# al3lg.net
KiCad netlist of a schematic drawn in EAGLE
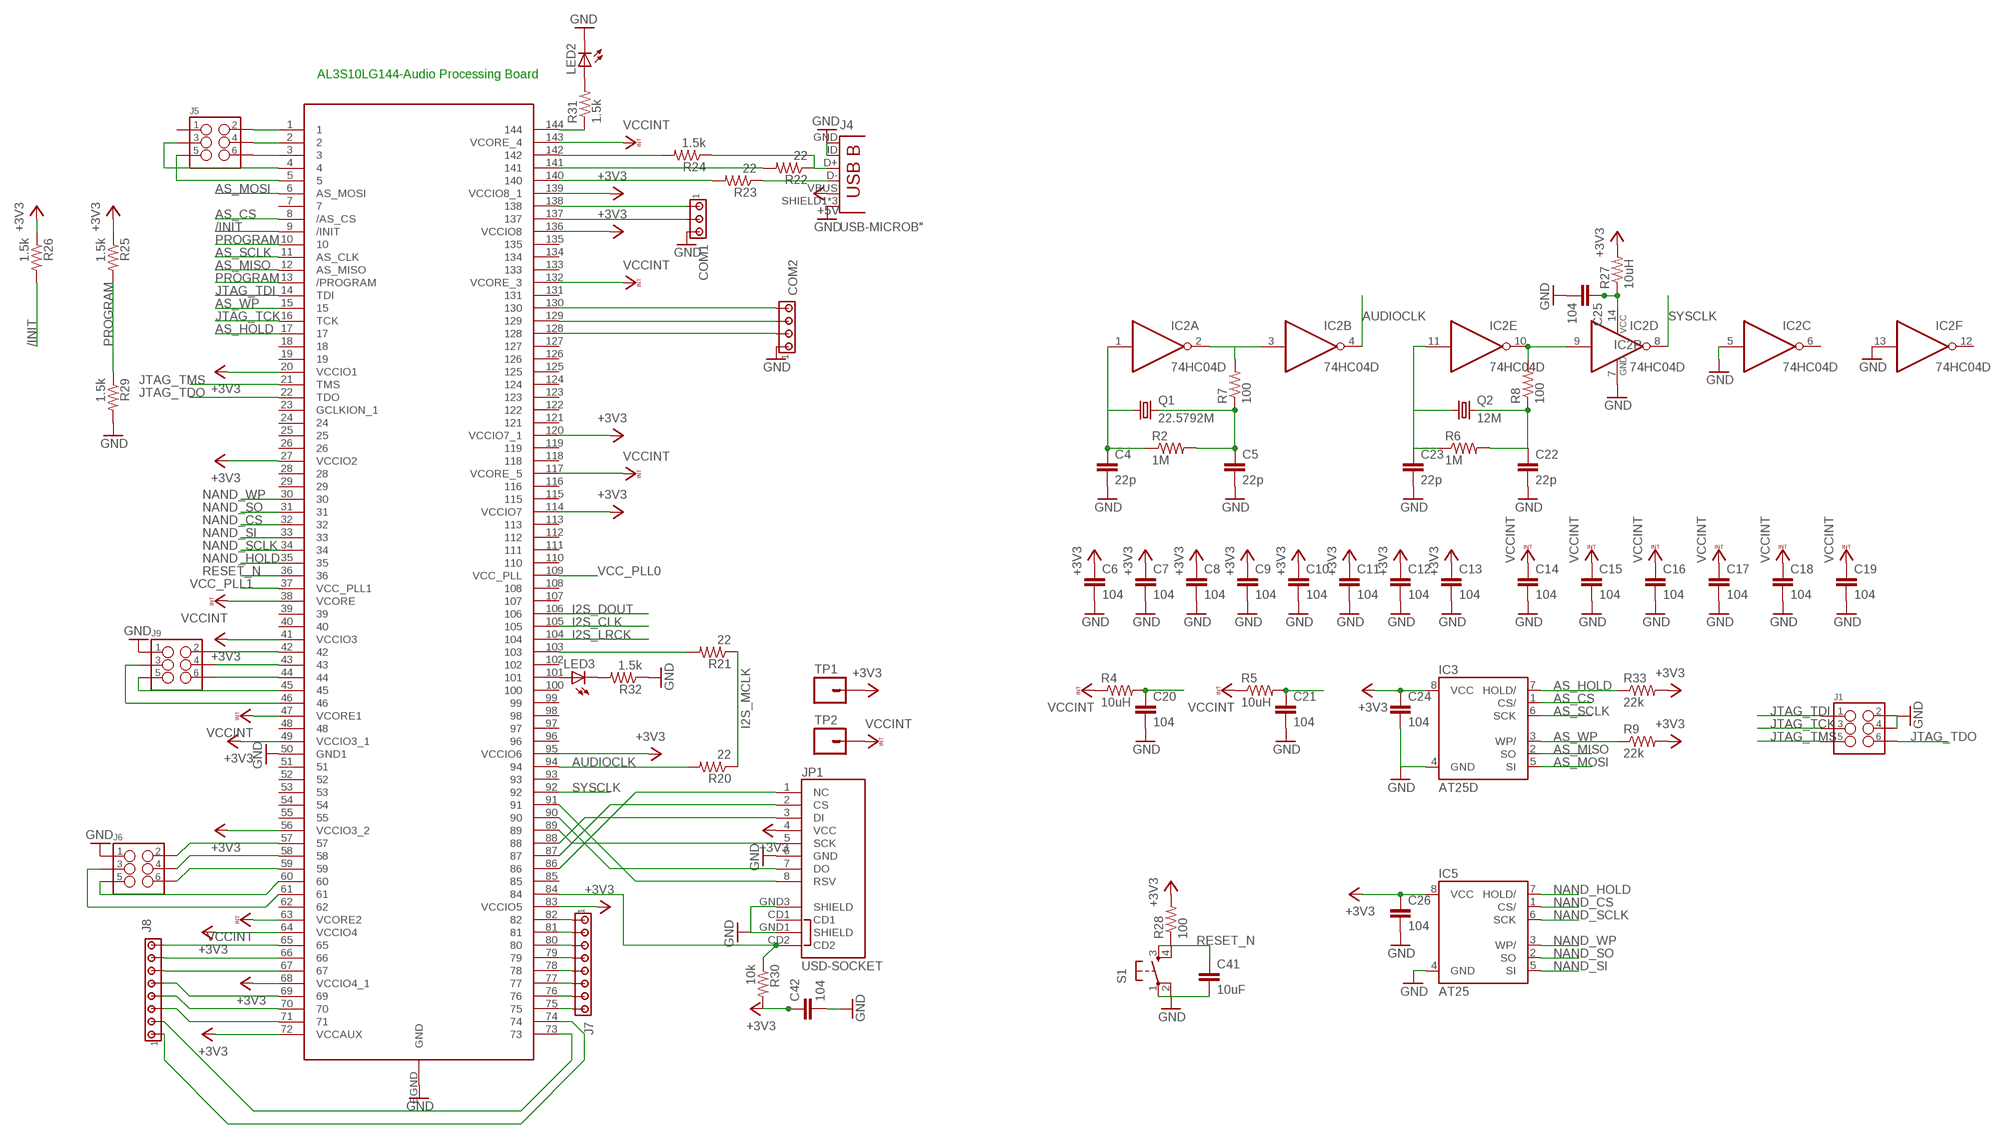
[diagram p0: schematic, sheet 1]
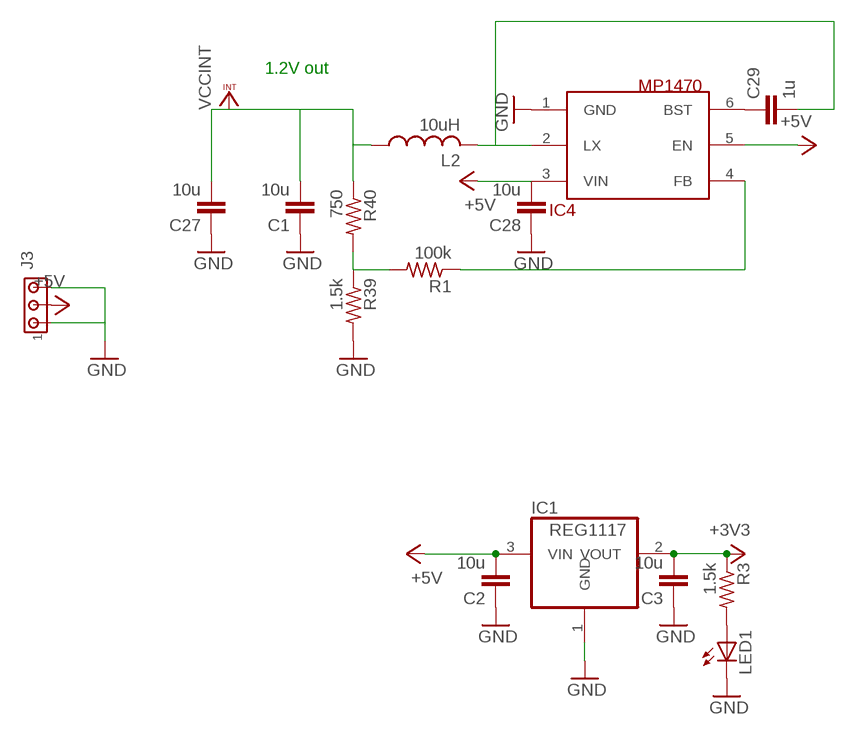
[diagram p1: schematic, sheet 2]
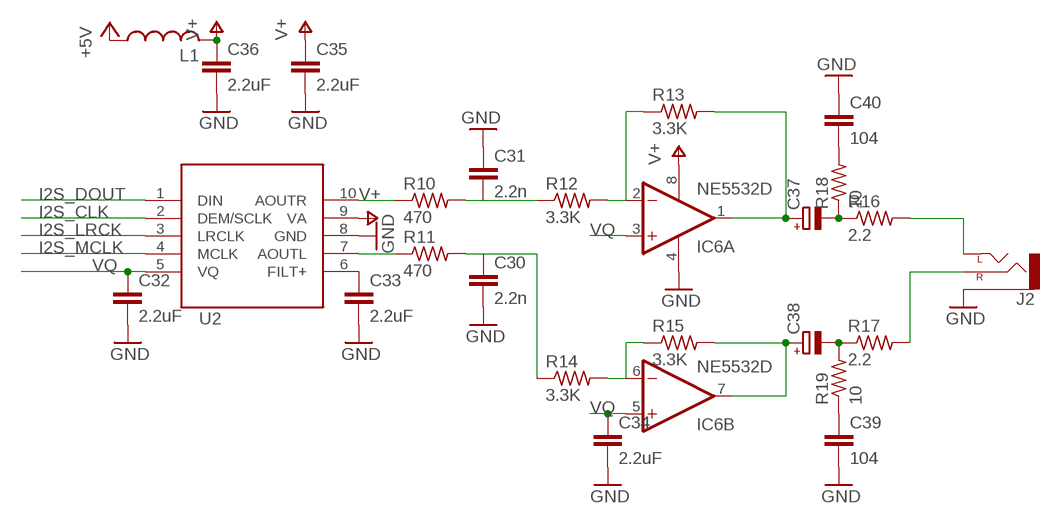
[diagram p2: schematic, sheet 3]

(export (version "E")
  (design (tool "Eeschema 10.0.6"))
  (components
    (comp (ref "C30")
      (value "2.2n")
      (footprint "eagle-import:C0805")
      (libsource (lib "eagle-import") (part "C-EUC0805"))
    )
    (comp (ref "C31")
      (value "2.2n")
      (footprint "eagle-import:C0805")
      (libsource (lib "eagle-import") (part "C-EUC0805"))
    )
    (comp (ref "C32")
      (value "2.2uF")
      (footprint "eagle-import:C0805")
      (libsource (lib "eagle-import") (part "C-EUC0805"))
    )
    (comp (ref "C33")
      (value "2.2uF")
      (footprint "eagle-import:C0805")
      (libsource (lib "eagle-import") (part "C-EUC0805"))
    )
    (comp (ref "C34")
      (value "2.2uF")
      (footprint "eagle-import:C0805")
      (libsource (lib "eagle-import") (part "C-EUC0805"))
    )
    (comp (ref "C35")
      (value "2.2uF")
      (footprint "eagle-import:C0805")
      (libsource (lib "eagle-import") (part "C-EUC0805"))
    )
    (comp (ref "C36")
      (value "2.2uF")
      (footprint "eagle-import:C0805")
      (libsource (lib "eagle-import") (part "C-EUC0805"))
    )
    (comp (ref "C37")
      (value "CPOL-EUE2.5-7")
      (footprint "eagle-import:E2,5-7")
      (libsource (lib "eagle-import") (part "CPOL-EUE2.5-7"))
    )
    (comp (ref "C38")
      (value "CPOL-EUE2.5-7")
      (footprint "eagle-import:E2,5-7")
      (libsource (lib "eagle-import") (part "CPOL-EUE2.5-7"))
    )
    (comp (ref "C39")
      (value "104")
      (footprint "eagle-import:C0805")
      (libsource (lib "eagle-import") (part "C-EUC0805"))
    )
    (comp (ref "C40")
      (value "104")
      (footprint "eagle-import:C0805")
      (libsource (lib "eagle-import") (part "C-EUC0805"))
    )
    (comp (ref "IC6")
      (value "NE5532D")
      (footprint "eagle-import:SO08")
      (libsource (lib "eagle-import") (part "NE5532D"))
    )
    (comp (ref "J2")
      (value "AUDIO-JACKPTH")
      (footprint "eagle-import:AUDIO-JACK")
      (libsource (lib "eagle-import") (part "AUDIO-JACKPTH"))
    )
    (comp (ref "L1")
      (value "L-USL4532P")
      (footprint "eagle-import:L4532P")
      (libsource (lib "eagle-import") (part "L-USL4532P"))
    )
    (comp (ref "R10")
      (value "470")
      (footprint "eagle-import:R0805")
      (libsource (lib "eagle-import") (part "R-US_R0805"))
    )
    (comp (ref "R11")
      (value "470")
      (footprint "eagle-import:R0805")
      (libsource (lib "eagle-import") (part "R-US_R0805"))
    )
    (comp (ref "R12")
      (value "3.3K")
      (footprint "eagle-import:R0805")
      (libsource (lib "eagle-import") (part "R-US_R0805"))
    )
    (comp (ref "R13")
      (value "3.3K")
      (footprint "eagle-import:R0805")
      (libsource (lib "eagle-import") (part "R-US_R0805"))
    )
    (comp (ref "R14")
      (value "3.3K")
      (footprint "eagle-import:R0805")
      (libsource (lib "eagle-import") (part "R-US_R0805"))
    )
    (comp (ref "R15")
      (value "3.3K")
      (footprint "eagle-import:R0805")
      (libsource (lib "eagle-import") (part "R-US_R0805"))
    )
    (comp (ref "R16")
      (value "2.2")
      (footprint "eagle-import:R0805")
      (libsource (lib "eagle-import") (part "R-US_R0805"))
    )
    (comp (ref "R17")
      (value "2.2")
      (footprint "eagle-import:R0805")
      (libsource (lib "eagle-import") (part "R-US_R0805"))
    )
    (comp (ref "R18")
      (value "10")
      (footprint "eagle-import:R0805")
      (libsource (lib "eagle-import") (part "R-US_R0805"))
    )
    (comp (ref "R19")
      (value "10")
      (footprint "eagle-import:R0805")
      (libsource (lib "eagle-import") (part "R-US_R0805"))
    )
    (comp (ref "U2")
      (value "CS4344")
      (footprint "eagle-import:TSSOP10")
      (libsource (lib "eagle-import") (part "CS4344"))
    )
    (comp (ref "C4")
      (value "22p")
      (footprint "eagle-import:C0805")
      (libsource (lib "eagle-import") (part "C-EUC0805"))
    )
    (comp (ref "C5")
      (value "22p")
      (footprint "eagle-import:C0805")
      (libsource (lib "eagle-import") (part "C-EUC0805"))
    )
    (comp (ref "C6")
      (value "104")
      (footprint "eagle-import:C0805")
      (libsource (lib "eagle-import") (part "C-EUC0805"))
    )
    (comp (ref "C7")
      (value "104")
      (footprint "eagle-import:C0805")
      (libsource (lib "eagle-import") (part "C-EUC0805"))
    )
    (comp (ref "C8")
      (value "104")
      (footprint "eagle-import:C0805")
      (libsource (lib "eagle-import") (part "C-EUC0805"))
    )
    (comp (ref "C9")
      (value "104")
      (footprint "eagle-import:C0805")
      (libsource (lib "eagle-import") (part "C-EUC0805"))
    )
    (comp (ref "C10")
      (value "104")
      (footprint "eagle-import:C0805")
      (libsource (lib "eagle-import") (part "C-EUC0805"))
    )
    (comp (ref "C11")
      (value "104")
      (footprint "eagle-import:C0805")
      (libsource (lib "eagle-import") (part "C-EUC0805"))
    )
    (comp (ref "C12")
      (value "104")
      (footprint "eagle-import:C0805")
      (libsource (lib "eagle-import") (part "C-EUC0805"))
    )
    (comp (ref "C13")
      (value "104")
      (footprint "eagle-import:C0805")
      (libsource (lib "eagle-import") (part "C-EUC0805"))
    )
    (comp (ref "C14")
      (value "104")
      (footprint "eagle-import:C0805")
      (libsource (lib "eagle-import") (part "C-EUC0805"))
    )
    (comp (ref "C15")
      (value "104")
      (footprint "eagle-import:C0805")
      (libsource (lib "eagle-import") (part "C-EUC0805"))
    )
    (comp (ref "C16")
      (value "104")
      (footprint "eagle-import:C0805")
      (libsource (lib "eagle-import") (part "C-EUC0805"))
    )
    (comp (ref "C17")
      (value "104")
      (footprint "eagle-import:C0805")
      (libsource (lib "eagle-import") (part "C-EUC0805"))
    )
    (comp (ref "C18")
      (value "104")
      (footprint "eagle-import:C0805")
      (libsource (lib "eagle-import") (part "C-EUC0805"))
    )
    (comp (ref "C19")
      (value "104")
      (footprint "eagle-import:C0805")
      (libsource (lib "eagle-import") (part "C-EUC0805"))
    )
    (comp (ref "C20")
      (value "104")
      (footprint "eagle-import:C0805")
      (libsource (lib "eagle-import") (part "C-EUC0805"))
    )
    (comp (ref "C21")
      (value "104")
      (footprint "eagle-import:C0805")
      (libsource (lib "eagle-import") (part "C-EUC0805"))
    )
    (comp (ref "C22")
      (value "22p")
      (footprint "eagle-import:C0805")
      (libsource (lib "eagle-import") (part "C-EUC0805"))
    )
    (comp (ref "C23")
      (value "22p")
      (footprint "eagle-import:C0805")
      (libsource (lib "eagle-import") (part "C-EUC0805"))
    )
    (comp (ref "C24")
      (value "104")
      (footprint "eagle-import:C0805")
      (libsource (lib "eagle-import") (part "C-EUC0805"))
    )
    (comp (ref "C25")
      (value "104")
      (footprint "eagle-import:C0805")
      (libsource (lib "eagle-import") (part "C-EUC0805"))
    )
    (comp (ref "C26")
      (value "104")
      (footprint "eagle-import:C0805")
      (libsource (lib "eagle-import") (part "C-EUC0805"))
    )
    (comp (ref "C41")
      (value "10uF")
      (footprint "eagle-import:C0805")
      (libsource (lib "eagle-import") (part "C-EUC0805"))
    )
    (comp (ref "C42")
      (value "104")
      (footprint "eagle-import:C0805")
      (libsource (lib "eagle-import") (part "C-EUC0805"))
    )
    (comp (ref "COM1")
      (value "MTA03-100")
      (footprint "eagle-import:10X03MTA")
      (libsource (lib "eagle-import") (part "MTA03-100"))
    )
    (comp (ref "COM2")
      (value "MTA04-100")
      (footprint "eagle-import:10X04MTA")
      (libsource (lib "eagle-import") (part "MTA04-100"))
    )
    (comp (ref "IC2")
      (value "74HC04D")
      (footprint "eagle-import:SO14")
      (libsource (lib "eagle-import") (part "7404DHC"))
    )
    (comp (ref "IC3")
      (value "AT25D")
      (footprint "eagle-import:SOIC8")
      (libsource (lib "eagle-import") (part "AT25D"))
    )
    (comp (ref "IC5")
      (value "AT25")
      (footprint "eagle-import:WSON8")
      (libsource (lib "eagle-import") (part "AT25"))
    )
    (comp (ref "J1")
      (value "M03X22X3_SILK_MALE_PTH")
      (footprint "eagle-import:2X3")
      (libsource (lib "eagle-import") (part "M03X22X3_SILK_MALE_PTH"))
    )
    (comp (ref "J4")
      (value "USB-MICROB\"")
      (footprint "eagle-import:USB-B-MICRO-SMD_V03")
      (libsource (lib "eagle-import") (part "USB-MICROB{dblquote}"))
    )
    (comp (ref "J5")
      (value "M03X22X3_SILK_MALE_PTH")
      (footprint "eagle-import:2X3")
      (libsource (lib "eagle-import") (part "M03X22X3_SILK_MALE_PTH"))
    )
    (comp (ref "J6")
      (value "M03X22X3_SILK_MALE_PTH")
      (footprint "eagle-import:2X3")
      (libsource (lib "eagle-import") (part "M03X22X3_SILK_MALE_PTH"))
    )
    (comp (ref "J7")
      (value "MTA08-100")
      (footprint "eagle-import:10X08MTA")
      (libsource (lib "eagle-import") (part "MTA08-100"))
    )
    (comp (ref "J8")
      (value "MTA08-100")
      (footprint "eagle-import:10X08MTA")
      (libsource (lib "eagle-import") (part "MTA08-100"))
    )
    (comp (ref "J9")
      (value "M03X22X3_SILK_MALE_PTH")
      (footprint "eagle-import:2X3")
      (libsource (lib "eagle-import") (part "M03X22X3_SILK_MALE_PTH"))
    )
    (comp (ref "JP1")
      (value "USD-SOCKET")
      (footprint "eagle-import:MICROSD_1_1")
      (libsource (lib "eagle-import") (part "USD-SOCKET"))
    )
    (comp (ref "LED2")
      (value "LEDSML0805")
      (footprint "eagle-import:SML0805")
      (libsource (lib "eagle-import") (part "LEDSML0805"))
    )
    (comp (ref "LED3")
      (value "LEDSML0805")
      (footprint "eagle-import:SML0805")
      (libsource (lib "eagle-import") (part "LEDSML0805"))
    )
    (comp (ref "Q1")
      (value "22.5792M")
      (footprint "eagle-import:HC49_S")
      (libsource (lib "eagle-import") (part "CRYSTALHC49S"))
    )
    (comp (ref "Q2")
      (value "12M")
      (footprint "eagle-import:HC49_S")
      (libsource (lib "eagle-import") (part "CRYSTALHC49S"))
    )
    (comp (ref "R2")
      (value "1M")
      (footprint "eagle-import:M0805")
      (libsource (lib "eagle-import") (part "R-US_M0805"))
    )
    (comp (ref "R4")
      (value "10uH")
      (footprint "eagle-import:M0805")
      (libsource (lib "eagle-import") (part "R-US_M0805"))
    )
    (comp (ref "R5")
      (value "10uH")
      (footprint "eagle-import:M0805")
      (libsource (lib "eagle-import") (part "R-US_M0805"))
    )
    (comp (ref "R6")
      (value "1M")
      (footprint "eagle-import:M0805")
      (libsource (lib "eagle-import") (part "R-US_M0805"))
    )
    (comp (ref "R7")
      (value "100")
      (footprint "eagle-import:M0805")
      (libsource (lib "eagle-import") (part "R-US_M0805"))
    )
    (comp (ref "R8")
      (value "100")
      (footprint "eagle-import:M0805")
      (libsource (lib "eagle-import") (part "R-US_M0805"))
    )
    (comp (ref "R9")
      (value "22k")
      (footprint "eagle-import:M0805")
      (libsource (lib "eagle-import") (part "R-US_M0805"))
    )
    (comp (ref "R20")
      (value "22")
      (footprint "eagle-import:M0805")
      (libsource (lib "eagle-import") (part "R-US_M0805"))
    )
    (comp (ref "R21")
      (value "22")
      (footprint "eagle-import:M0805")
      (libsource (lib "eagle-import") (part "R-US_M0805"))
    )
    (comp (ref "R22")
      (value "22")
      (footprint "eagle-import:M0805")
      (libsource (lib "eagle-import") (part "R-US_M0805"))
    )
    (comp (ref "R23")
      (value "22")
      (footprint "eagle-import:M0805")
      (libsource (lib "eagle-import") (part "R-US_M0805"))
    )
    (comp (ref "R24")
      (value "1.5k")
      (footprint "eagle-import:M0805")
      (libsource (lib "eagle-import") (part "R-US_M0805"))
    )
    (comp (ref "R25")
      (value "1.5k")
      (footprint "eagle-import:M0805")
      (libsource (lib "eagle-import") (part "R-US_M0805"))
    )
    (comp (ref "R26")
      (value "1.5k")
      (footprint "eagle-import:M0805")
      (libsource (lib "eagle-import") (part "R-US_M0805"))
    )
    (comp (ref "R27")
      (value "10uH")
      (footprint "eagle-import:M0805")
      (libsource (lib "eagle-import") (part "R-US_M0805"))
    )
    (comp (ref "R28")
      (value "100")
      (footprint "eagle-import:M0805")
      (libsource (lib "eagle-import") (part "R-US_M0805"))
    )
    (comp (ref "R29")
      (value "1.5k")
      (footprint "eagle-import:M0805")
      (libsource (lib "eagle-import") (part "R-US_M0805"))
    )
    (comp (ref "R30")
      (value "10k")
      (footprint "eagle-import:M0805")
      (libsource (lib "eagle-import") (part "R-US_M0805"))
    )
    (comp (ref "R31")
      (value "1.5k")
      (footprint "eagle-import:R0805")
      (libsource (lib "eagle-import") (part "R-US_R0805"))
    )
    (comp (ref "R32")
      (value "1.5k")
      (footprint "eagle-import:R0805")
      (libsource (lib "eagle-import") (part "R-US_R0805"))
    )
    (comp (ref "R33")
      (value "22k")
      (footprint "eagle-import:M0805")
      (libsource (lib "eagle-import") (part "R-US_M0805"))
    )
    (comp (ref "S1")
      (value "10-XXSMD")
      (footprint "eagle-import:B3F-10SMD")
      (libsource (lib "eagle-import") (part "10-XXSMD"))
    )
    (comp (ref "TP1")
      (value "M01")
      (footprint "eagle-import:0805SMD")
      (libsource (lib "eagle-import") (part "M01"))
    )
    (comp (ref "TP2")
      (value "M01")
      (footprint "eagle-import:0805SMD")
      (libsource (lib "eagle-import") (part "M01"))
    )
    (comp (ref "U1")
      (value "AL3S10LG144")
      (footprint "eagle-import:HLQFP144NT16")
      (libsource (lib "eagle-import") (part "AL3S10LG144"))
    )
    (comp (ref "C1")
      (value "10u")
      (footprint "eagle-import:C0805")
      (libsource (lib "eagle-import") (part "C-EUC0805"))
    )
    (comp (ref "C2")
      (value "10u")
      (footprint "eagle-import:C0805")
      (libsource (lib "eagle-import") (part "C-EUC0805"))
    )
    (comp (ref "C3")
      (value "10u")
      (footprint "eagle-import:C0805")
      (libsource (lib "eagle-import") (part "C-EUC0805"))
    )
    (comp (ref "C27")
      (value "10u")
      (footprint "eagle-import:C0805")
      (libsource (lib "eagle-import") (part "C-EUC0805"))
    )
    (comp (ref "C28")
      (value "10u")
      (footprint "eagle-import:C0805")
      (libsource (lib "eagle-import") (part "C-EUC0805"))
    )
    (comp (ref "C29")
      (value "1u")
      (footprint "eagle-import:C0805")
      (libsource (lib "eagle-import") (part "C-EUC0805"))
    )
    (comp (ref "IC1")
      (value "REG1117")
      (footprint "eagle-import:SOT223")
      (libsource (lib "eagle-import") (part "REG1117"))
    )
    (comp (ref "IC4")
      (value "MP1470")
      (footprint "eagle-import:SOT23-6L")
      (libsource (lib "eagle-import") (part "MP1470"))
    )
    (comp (ref "J3")
      (value "MTA03-100")
      (footprint "eagle-import:10X03MTA")
      (libsource (lib "eagle-import") (part "MTA03-100"))
    )
    (comp (ref "L2")
      (value "10uH")
      (footprint "eagle-import:L4532P")
      (libsource (lib "eagle-import") (part "L-USL4532P"))
    )
    (comp (ref "LED1")
      (value "LEDSML0805")
      (footprint "eagle-import:SML0805")
      (libsource (lib "eagle-import") (part "LEDSML0805"))
    )
    (comp (ref "R1")
      (value "100k")
      (footprint "eagle-import:R0805")
      (libsource (lib "eagle-import") (part "R-US_R0805"))
    )
    (comp (ref "R3")
      (value "1.5k")
      (footprint "eagle-import:R0805")
      (libsource (lib "eagle-import") (part "R-US_R0805"))
    )
    (comp (ref "R39")
      (value "1.5k")
      (footprint "eagle-import:R0805")
      (libsource (lib "eagle-import") (part "R-US_R0805"))
    )
    (comp (ref "R40")
      (value "750")
      (footprint "eagle-import:R0805")
      (libsource (lib "eagle-import") (part "R-US_R0805"))
    )
  )
  (nets
    (net (code "1") (name "+3V3") (class "Default")
      (node (ref "C10") (pin "1") (pinfunction "1_1") (pintype "passive"))
      (node (ref "C11") (pin "1") (pinfunction "1_1") (pintype "passive"))
      (node (ref "C12") (pin "1") (pinfunction "1_1") (pintype "passive"))
      (node (ref "C13") (pin "1") (pinfunction "1_1") (pintype "passive"))
      (node (ref "C24") (pin "1") (pinfunction "1_1") (pintype "passive"))
      (node (ref "C26") (pin "1") (pinfunction "1_1") (pintype "passive"))
      (node (ref "C3") (pin "2") (pinfunction "2_2") (pintype "passive"))
      (node (ref "C42") (pin "1") (pinfunction "1_1") (pintype "passive"))
      (node (ref "C6") (pin "1") (pinfunction "1_1") (pintype "passive"))
      (node (ref "C7") (pin "1") (pinfunction "1_1") (pintype "passive"))
      (node (ref "C8") (pin "1") (pinfunction "1_1") (pintype "passive"))
      (node (ref "C9") (pin "1") (pinfunction "1_1") (pintype "passive"))
      (node (ref "IC1") (pin "2") (pinfunction "VOUT_2") (pintype "output"))
      (node (ref "IC3") (pin "8") (pinfunction "VCC_8") (pintype "power_in"))
      (node (ref "IC5") (pin "8") (pinfunction "VCC_8") (pintype "power_in"))
      (node (ref "JP1") (pin "4") (pinfunction "VCC_4") (pintype "bidirectional"))
      (node (ref "R25") (pin "1") (pinfunction "1_1") (pintype "passive"))
      (node (ref "R26") (pin "1") (pinfunction "1_1") (pintype "passive"))
      (node (ref "R27") (pin "2") (pinfunction "2_2") (pintype "passive"))
      (node (ref "R28") (pin "2") (pinfunction "2_2") (pintype "passive"))
      (node (ref "R3") (pin "1") (pinfunction "1_1") (pintype "passive"))
      (node (ref "R30") (pin "2") (pinfunction "2_2") (pintype "passive"))
      (node (ref "R33") (pin "2") (pinfunction "2_2") (pintype "passive"))
      (node (ref "R9") (pin "2") (pinfunction "2_2") (pintype "passive"))
      (node (ref "TP1") (pin "1") (pinfunction "1_1") (pintype "passive"))
      (node (ref "U1") (pin "114") (pinfunction "VCCIO7_114") (pintype "bidirectional"))
      (node (ref "U1") (pin "120") (pinfunction "VCCIO7_1_120") (pintype "bidirectional"))
      (node (ref "U1") (pin "136") (pinfunction "VCCIO8_136") (pintype "bidirectional"))
      (node (ref "U1") (pin "139") (pinfunction "VCCIO8_1_139") (pintype "bidirectional"))
      (node (ref "U1") (pin "20") (pinfunction "VCCIO1_20") (pintype "bidirectional"))
      (node (ref "U1") (pin "27") (pinfunction "VCCIO2_27") (pintype "bidirectional"))
      (node (ref "U1") (pin "41") (pinfunction "VCCIO3_41") (pintype "bidirectional"))
      (node (ref "U1") (pin "49") (pinfunction "VCCIO3_1_49") (pintype "bidirectional"))
      (node (ref "U1") (pin "56") (pinfunction "VCCIO3_2_56") (pintype "bidirectional"))
      (node (ref "U1") (pin "64") (pinfunction "VCCIO4_64") (pintype "bidirectional"))
      (node (ref "U1") (pin "68") (pinfunction "VCCIO4_1_68") (pintype "bidirectional"))
      (node (ref "U1") (pin "72") (pinfunction "VCCAUX_72") (pintype "bidirectional"))
      (node (ref "U1") (pin "83") (pinfunction "VCCIO5_83") (pintype "bidirectional"))
      (node (ref "U1") (pin "95") (pinfunction "VCCIO6_95") (pintype "bidirectional"))
    )
    (net (code "2") (name "+5V") (class "Default")
      (node (ref "C2") (pin "2") (pinfunction "2_2") (pintype "passive"))
      (node (ref "C28") (pin "2") (pinfunction "2_2") (pintype "passive"))
      (node (ref "IC1") (pin "3") (pinfunction "VIN_3") (pintype "input"))
      (node (ref "IC4") (pin "3") (pinfunction "VIN_3") (pintype "power_in"))
      (node (ref "IC4") (pin "5") (pinfunction "EN_5") (pintype "bidirectional"))
      (node (ref "J3") (pin "2") (pinfunction "2_2") (pintype "passive"))
      (node (ref "J4") (pin "VBUS") (pinfunction "VBUS_VBUS") (pintype "bidirectional"))
      (node (ref "L1") (pin "1") (pinfunction "1_1") (pintype "passive"))
    )
    (net (code "3") (name "AS_CS") (class "Default")
      (node (ref "IC3") (pin "1") (pinfunction "CS/_1") (pintype "input"))
      (node (ref "U1") (pin "8") (pinfunction "/AS_CS_8") (pintype "bidirectional"))
    )
    (net (code "4") (name "AS_HOLD") (class "Default")
      (node (ref "IC3") (pin "7") (pinfunction "HOLD/_7") (pintype "input"))
      (node (ref "R33") (pin "1") (pinfunction "1_1") (pintype "passive"))
      (node (ref "U1") (pin "17") (pinfunction "17_17") (pintype "bidirectional"))
    )
    (net (code "5") (name "AS_MISO") (class "Default")
      (node (ref "IC3") (pin "2") (pinfunction "SO_2") (pintype "input"))
      (node (ref "U1") (pin "12") (pinfunction "AS_MISO_12") (pintype "bidirectional"))
    )
    (net (code "6") (name "AS_MOSI") (class "Default")
      (node (ref "IC3") (pin "5") (pinfunction "SI_5") (pintype "bidirectional"))
      (node (ref "U1") (pin "6") (pinfunction "AS_MOSI_6") (pintype "bidirectional"))
    )
    (net (code "7") (name "AS_SCLK") (class "Default")
      (node (ref "IC3") (pin "6") (pinfunction "SCK_6") (pintype "bidirectional"))
      (node (ref "U1") (pin "11") (pinfunction "AS_CLK_11") (pintype "bidirectional"))
    )
    (net (code "8") (name "AS_WP") (class "Default")
      (node (ref "IC3") (pin "3") (pinfunction "WP/_3") (pintype "input"))
      (node (ref "R9") (pin "1") (pinfunction "1_1") (pintype "passive"))
      (node (ref "U1") (pin "15") (pinfunction "15_15") (pintype "bidirectional"))
    )
    (net (code "9") (name "AUDIOCLK") (class "Default")
      (node (ref "IC2") (pin "4") (pinfunction "O_4") (pintype "output"))
      (node (ref "R20") (pin "2") (pinfunction "2_2") (pintype "passive"))
      (node (ref "U1") (pin "94") (pinfunction "94_94") (pintype "bidirectional"))
    )
    (net (code "10") (name "GND") (class "Default")
      (node (ref "C1") (pin "1") (pinfunction "1_1") (pintype "passive"))
      (node (ref "C10") (pin "2") (pinfunction "2_2") (pintype "passive"))
      (node (ref "C11") (pin "2") (pinfunction "2_2") (pintype "passive"))
      (node (ref "C12") (pin "2") (pinfunction "2_2") (pintype "passive"))
      (node (ref "C13") (pin "2") (pinfunction "2_2") (pintype "passive"))
      (node (ref "C14") (pin "2") (pinfunction "2_2") (pintype "passive"))
      (node (ref "C15") (pin "2") (pinfunction "2_2") (pintype "passive"))
      (node (ref "C16") (pin "2") (pinfunction "2_2") (pintype "passive"))
      (node (ref "C17") (pin "2") (pinfunction "2_2") (pintype "passive"))
      (node (ref "C18") (pin "2") (pinfunction "2_2") (pintype "passive"))
      (node (ref "C19") (pin "2") (pinfunction "2_2") (pintype "passive"))
      (node (ref "C2") (pin "1") (pinfunction "1_1") (pintype "passive"))
      (node (ref "C20") (pin "2") (pinfunction "2_2") (pintype "passive"))
      (node (ref "C21") (pin "2") (pinfunction "2_2") (pintype "passive"))
      (node (ref "C22") (pin "2") (pinfunction "2_2") (pintype "passive"))
      (node (ref "C23") (pin "2") (pinfunction "2_2") (pintype "passive"))
      (node (ref "C24") (pin "2") (pinfunction "2_2") (pintype "passive"))
      (node (ref "C25") (pin "2") (pinfunction "2_2") (pintype "passive"))
      (node (ref "C26") (pin "2") (pinfunction "2_2") (pintype "passive"))
      (node (ref "C27") (pin "1") (pinfunction "1_1") (pintype "passive"))
      (node (ref "C28") (pin "1") (pinfunction "1_1") (pintype "passive"))
      (node (ref "C3") (pin "1") (pinfunction "1_1") (pintype "passive"))
      (node (ref "C30") (pin "2") (pinfunction "2_2") (pintype "passive"))
      (node (ref "C31") (pin "1") (pinfunction "1_1") (pintype "passive"))
      (node (ref "C32") (pin "2") (pinfunction "2_2") (pintype "passive"))
      (node (ref "C33") (pin "2") (pinfunction "2_2") (pintype "passive"))
      (node (ref "C34") (pin "2") (pinfunction "2_2") (pintype "passive"))
      (node (ref "C35") (pin "2") (pinfunction "2_2") (pintype "passive"))
      (node (ref "C36") (pin "2") (pinfunction "2_2") (pintype "passive"))
      (node (ref "C39") (pin "2") (pinfunction "2_2") (pintype "passive"))
      (node (ref "C4") (pin "2") (pinfunction "2_2") (pintype "passive"))
      (node (ref "C40") (pin "1") (pinfunction "1_1") (pintype "passive"))
      (node (ref "C41") (pin "2") (pinfunction "2_2") (pintype "passive"))
      (node (ref "C42") (pin "2") (pinfunction "2_2") (pintype "passive"))
      (node (ref "C5") (pin "2") (pinfunction "2_2") (pintype "passive"))
      (node (ref "C6") (pin "2") (pinfunction "2_2") (pintype "passive"))
      (node (ref "C7") (pin "2") (pinfunction "2_2") (pintype "passive"))
      (node (ref "C8") (pin "2") (pinfunction "2_2") (pintype "passive"))
      (node (ref "C9") (pin "2") (pinfunction "2_2") (pintype "passive"))
      (node (ref "COM1") (pin "3") (pinfunction "3_3") (pintype "passive"))
      (node (ref "COM2") (pin "1") (pinfunction "1_1") (pintype "passive"))
      (node (ref "IC1") (pin "1") (pinfunction "GND_1") (pintype "power_in"))
      (node (ref "IC2") (pin "13") (pinfunction "I_13") (pintype "input"))
      (node (ref "IC2") (pin "5") (pinfunction "I_5") (pintype "input"))
      (node (ref "IC2") (pin "7") (pinfunction "GND_7") (pintype "power_in"))
      (node (ref "IC3") (pin "4") (pinfunction "GND_4") (pintype "power_in"))
      (node (ref "IC4") (pin "1") (pinfunction "GND_1") (pintype "power_in"))
      (node (ref "IC5") (pin "4") (pinfunction "GND_4") (pintype "power_in"))
      (node (ref "IC6") (pin "4") (pinfunction "V-_4") (pintype "power_in"))
      (node (ref "J1") (pin "2") (pinfunction "2_2") (pintype "bidirectional"))
      (node (ref "J1") (pin "4") (pinfunction "4_4") (pintype "bidirectional"))
      (node (ref "J2") (pin "SLEEVE") (pinfunction "SLEEVE_SLEEVE") (pintype "bidirectional"))
      (node (ref "J3") (pin "1") (pinfunction "1_1") (pintype "passive"))
      (node (ref "J3") (pin "3") (pinfunction "3_3") (pintype "passive"))
      (node (ref "J4") (pin "GND") (pinfunction "GND_GND") (pintype "bidirectional"))
      (node (ref "J4") (pin "ID") (pinfunction "USBID_ID") (pintype "bidirectional"))
      (node (ref "J4") (pin "SHIELD1") (pinfunction "SHIELD_SHIELD1") (pintype "bidirectional"))
      (node (ref "J4") (pin "SHIELD2") (pinfunction "SHIELD_SHIELD2") (pintype "bidirectional"))
      (node (ref "J4") (pin "SHIELD3") (pinfunction "SHIELD_SHIELD3") (pintype "bidirectional"))
      (node (ref "J6") (pin "1") (pinfunction "1_1") (pintype "bidirectional"))
      (node (ref "J9") (pin "1") (pinfunction "1_1") (pintype "bidirectional"))
      (node (ref "JP1") (pin "6") (pinfunction "GND_6") (pintype "bidirectional"))
      (node (ref "JP1") (pin "GND1") (pinfunction "SHIELD_GND1") (pintype "bidirectional"))
      (node (ref "JP1") (pin "GND3") (pinfunction "SHIELD_GND3") (pintype "bidirectional"))
      (node (ref "LED1") (pin "C") (pinfunction "C_C") (pintype "passive"))
      (node (ref "LED2") (pin "C") (pinfunction "C_C") (pintype "passive"))
      (node (ref "R29") (pin "2") (pinfunction "2_2") (pintype "passive"))
      (node (ref "R32") (pin "1") (pinfunction "1_1") (pintype "passive"))
      (node (ref "R39") (pin "2") (pinfunction "2_2") (pintype "passive"))
      (node (ref "S1") (pin "1") (pinfunction "P_1") (pintype "passive"))
      (node (ref "S1") (pin "2") (pinfunction "P1_2") (pintype "passive"))
      (node (ref "U1") (pin "50") (pinfunction "GND1_50") (pintype "bidirectional"))
      (node (ref "U1") (pin "EGND") (pinfunction "GND_EGND") (pintype "bidirectional"))
      (node (ref "U2") (pin "8") (pinfunction "GND_8") (pintype "bidirectional"))
    )
    (net (code "11") (name "I2S_CLK") (class "Default")
      (node (ref "U1") (pin "105") (pinfunction "105_105") (pintype "bidirectional"))
      (node (ref "U2") (pin "2") (pinfunction "DEM/SCLK_2") (pintype "bidirectional"))
    )
    (net (code "12") (name "I2S_DOUT") (class "Default")
      (node (ref "U1") (pin "106") (pinfunction "106_106") (pintype "bidirectional"))
      (node (ref "U2") (pin "1") (pinfunction "DIN_1") (pintype "bidirectional"))
    )
    (net (code "13") (name "I2S_LRCK") (class "Default")
      (node (ref "U1") (pin "104") (pinfunction "104_104") (pintype "bidirectional"))
      (node (ref "U2") (pin "3") (pinfunction "LRCLK_3") (pintype "bidirectional"))
    )
    (net (code "14") (name "I2S_MCLK") (class "Default")
      (node (ref "R20") (pin "1") (pinfunction "1_1") (pintype "passive"))
      (node (ref "R21") (pin "1") (pinfunction "1_1") (pintype "passive"))
      (node (ref "U2") (pin "4") (pinfunction "MCLK_4") (pintype "bidirectional"))
    )
    (net (code "15") (name "JTAG_TCK") (class "Default")
      (node (ref "J1") (pin "3") (pinfunction "3_3") (pintype "bidirectional"))
      (node (ref "U1") (pin "16") (pinfunction "TCK_16") (pintype "bidirectional"))
    )
    (net (code "16") (name "JTAG_TDI") (class "Default")
      (node (ref "J1") (pin "1") (pinfunction "1_1") (pintype "bidirectional"))
      (node (ref "U1") (pin "14") (pinfunction "TDI_14") (pintype "bidirectional"))
    )
    (net (code "17") (name "JTAG_TDO") (class "Default")
      (node (ref "J1") (pin "6") (pinfunction "6_6") (pintype "bidirectional"))
      (node (ref "U1") (pin "22") (pinfunction "TDO_22") (pintype "bidirectional"))
    )
    (net (code "18") (name "JTAG_TMS") (class "Default")
      (node (ref "J1") (pin "5") (pinfunction "5_5") (pintype "bidirectional"))
      (node (ref "U1") (pin "21") (pinfunction "TMS_21") (pintype "bidirectional"))
    )
    (net (code "19") (name "NAND_CS") (class "Default")
      (node (ref "IC5") (pin "1") (pinfunction "CS/_1") (pintype "input"))
      (node (ref "U1") (pin "32") (pinfunction "32_32") (pintype "bidirectional"))
    )
    (net (code "20") (name "NAND_HOLD") (class "Default")
      (node (ref "IC5") (pin "7") (pinfunction "HOLD/_7") (pintype "input"))
      (node (ref "U1") (pin "35") (pinfunction "35_35") (pintype "bidirectional"))
    )
    (net (code "21") (name "NAND_SCLK") (class "Default")
      (node (ref "IC5") (pin "6") (pinfunction "SCK_6") (pintype "bidirectional"))
      (node (ref "U1") (pin "34") (pinfunction "34_34") (pintype "bidirectional"))
    )
    (net (code "22") (name "NAND_SI") (class "Default")
      (node (ref "IC5") (pin "5") (pinfunction "SI_5") (pintype "bidirectional"))
      (node (ref "U1") (pin "33") (pinfunction "33_33") (pintype "bidirectional"))
    )
    (net (code "23") (name "NAND_SO") (class "Default")
      (node (ref "IC5") (pin "2") (pinfunction "SO_2") (pintype "input"))
      (node (ref "U1") (pin "31") (pinfunction "31_31") (pintype "bidirectional"))
    )
    (net (code "24") (name "NAND_WP") (class "Default")
      (node (ref "IC5") (pin "3") (pinfunction "WP/_3") (pintype "input"))
      (node (ref "U1") (pin "30") (pinfunction "30_30") (pintype "bidirectional"))
    )
    (net (code "25") (name "Net-(C5-Pad1)") (class "Default")
      (node (ref "C5") (pin "1") (pinfunction "1_1") (pintype "passive"))
      (node (ref "Q1") (pin "2") (pinfunction "2_2") (pintype "passive"))
      (node (ref "R2") (pin "2") (pinfunction "2_2") (pintype "passive"))
      (node (ref "R7") (pin "1") (pinfunction "1_1") (pintype "passive"))
    )
    (net (code "26") (name "Net-(C22-Pad1)") (class "Default")
      (node (ref "C22") (pin "1") (pinfunction "1_1") (pintype "passive"))
      (node (ref "Q2") (pin "2") (pinfunction "2_2") (pintype "passive"))
      (node (ref "R6") (pin "2") (pinfunction "2_2") (pintype "passive"))
      (node (ref "R8") (pin "1") (pinfunction "1_1") (pintype "passive"))
    )
    (net (code "27") (name "Net-(C30-Pad1)") (class "Default")
      (node (ref "C30") (pin "1") (pinfunction "1_1") (pintype "passive"))
      (node (ref "R11") (pin "2") (pinfunction "2_2") (pintype "passive"))
      (node (ref "R14") (pin "1") (pinfunction "1_1") (pintype "passive"))
    )
    (net (code "28") (name "Net-(C31-Pad2)") (class "Default")
      (node (ref "C31") (pin "2") (pinfunction "2_2") (pintype "passive"))
      (node (ref "R10") (pin "2") (pinfunction "2_2") (pintype "passive"))
      (node (ref "R12") (pin "1") (pinfunction "1_1") (pintype "passive"))
    )
    (net (code "29") (name "Net-(C37-Pad-)") (class "Default")
      (node (ref "C37") (pin "-") (pinfunction "-_-") (pintype "passive"))
      (node (ref "R16") (pin "1") (pinfunction "1_1") (pintype "passive"))
      (node (ref "R18") (pin "1") (pinfunction "1_1") (pintype "passive"))
    )
    (net (code "30") (name "Net-(C38-Pad-)") (class "Default")
      (node (ref "C38") (pin "-") (pinfunction "-_-") (pintype "passive"))
      (node (ref "R17") (pin "1") (pinfunction "1_1") (pintype "passive"))
      (node (ref "R19") (pin "2") (pinfunction "2_2") (pintype "passive"))
    )
    (net (code "31") (name "Net-(C39-Pad1)") (class "Default")
      (node (ref "C39") (pin "1") (pinfunction "1_1") (pintype "passive"))
      (node (ref "R19") (pin "1") (pinfunction "1_1") (pintype "passive"))
    )
    (net (code "32") (name "Net-(C40-Pad2)") (class "Default")
      (node (ref "C40") (pin "2") (pinfunction "2_2") (pintype "passive"))
      (node (ref "R18") (pin "2") (pinfunction "2_2") (pintype "passive"))
    )
    (net (code "33") (name "Net-(COM1-Pad1)") (class "Default")
      (node (ref "COM1") (pin "1") (pinfunction "1_1") (pintype "passive"))
      (node (ref "U1") (pin "138") (pinfunction "138_138") (pintype "bidirectional"))
    )
    (net (code "34") (name "Net-(COM1-Pad2)") (class "Default")
      (node (ref "COM1") (pin "2") (pinfunction "2_2") (pintype "passive"))
      (node (ref "U1") (pin "137") (pinfunction "137_137") (pintype "bidirectional"))
    )
    (net (code "35") (name "Net-(COM2-Pad2)") (class "Default")
      (node (ref "COM2") (pin "2") (pinfunction "2_2") (pintype "passive"))
      (node (ref "U1") (pin "128") (pinfunction "128_128") (pintype "bidirectional"))
    )
    (net (code "36") (name "Net-(COM2-Pad3)") (class "Default")
      (node (ref "COM2") (pin "3") (pinfunction "3_3") (pintype "passive"))
      (node (ref "U1") (pin "129") (pinfunction "129_129") (pintype "bidirectional"))
    )
    (net (code "37") (name "Net-(COM2-Pad4)") (class "Default")
      (node (ref "COM2") (pin "4") (pinfunction "4_4") (pintype "passive"))
      (node (ref "U1") (pin "130") (pinfunction "130_130") (pintype "bidirectional"))
    )
    (net (code "38") (name "Net-(IC2A-I)") (class "Default")
      (node (ref "C4") (pin "1") (pinfunction "1_1") (pintype "passive"))
      (node (ref "IC2") (pin "1") (pinfunction "I_1") (pintype "input"))
      (node (ref "Q1") (pin "1") (pinfunction "1_1") (pintype "passive"))
      (node (ref "R2") (pin "1") (pinfunction "1_1") (pintype "passive"))
    )
    (net (code "39") (name "Net-(IC2A-O)") (class "Default")
      (node (ref "IC2") (pin "2") (pinfunction "O_2") (pintype "output"))
      (node (ref "IC2") (pin "3") (pinfunction "I_3") (pintype "input"))
      (node (ref "R7") (pin "2") (pinfunction "2_2") (pintype "passive"))
    )
    (net (code "40") (name "Net-(IC2D-I)") (class "Default")
      (node (ref "IC2") (pin "10") (pinfunction "O_10") (pintype "output"))
      (node (ref "IC2") (pin "9") (pinfunction "I_9") (pintype "input"))
      (node (ref "R8") (pin "2") (pinfunction "2_2") (pintype "passive"))
    )
    (net (code "41") (name "Net-(IC2E-I)") (class "Default")
      (node (ref "C23") (pin "1") (pinfunction "1_1") (pintype "passive"))
      (node (ref "IC2") (pin "11") (pinfunction "I_11") (pintype "input"))
      (node (ref "Q2") (pin "1") (pinfunction "1_1") (pintype "passive"))
      (node (ref "R6") (pin "1") (pinfunction "1_1") (pintype "passive"))
    )
    (net (code "42") (name "Net-(IC2G-VCC)") (class "Default")
      (node (ref "C25") (pin "1") (pinfunction "1_1") (pintype "passive"))
      (node (ref "IC2") (pin "14") (pinfunction "VCC_14") (pintype "power_in"))
      (node (ref "R27") (pin "1") (pinfunction "1_1") (pintype "passive"))
    )
    (net (code "43") (name "Net-(IC4-BST)") (class "Default")
      (node (ref "C29") (pin "1") (pinfunction "1_1") (pintype "passive"))
      (node (ref "IC4") (pin "6") (pinfunction "BST_6") (pintype "bidirectional"))
    )
    (net (code "44") (name "Net-(IC4-FB)") (class "Default")
      (node (ref "IC4") (pin "4") (pinfunction "FB_4") (pintype "bidirectional"))
      (node (ref "R1") (pin "1") (pinfunction "1_1") (pintype "passive"))
    )
    (net (code "45") (name "Net-(IC4-LX)") (class "Default")
      (node (ref "C29") (pin "2") (pinfunction "2_2") (pintype "passive"))
      (node (ref "IC4") (pin "2") (pinfunction "LX_2") (pintype "output"))
      (node (ref "L2") (pin "2") (pinfunction "2_2") (pintype "passive"))
    )
    (net (code "46") (name "Net-(IC6A--IN)") (class "Default")
      (node (ref "IC6") (pin "2") (pinfunction "-IN_2") (pintype "input"))
      (node (ref "R12") (pin "2") (pinfunction "2_2") (pintype "passive"))
      (node (ref "R13") (pin "1") (pinfunction "1_1") (pintype "passive"))
    )
    (net (code "47") (name "Net-(IC6A-OUT)") (class "Default")
      (node (ref "C37") (pin "+") (pinfunction "+_+") (pintype "passive"))
      (node (ref "IC6") (pin "1") (pinfunction "OUT_1") (pintype "output"))
      (node (ref "R13") (pin "2") (pinfunction "2_2") (pintype "passive"))
    )
    (net (code "48") (name "Net-(IC6B--IN)") (class "Default")
      (node (ref "IC6") (pin "6") (pinfunction "-IN_6") (pintype "input"))
      (node (ref "R14") (pin "2") (pinfunction "2_2") (pintype "passive"))
      (node (ref "R15") (pin "1") (pinfunction "1_1") (pintype "passive"))
    )
    (net (code "49") (name "Net-(IC6B-OUT)") (class "Default")
      (node (ref "C38") (pin "+") (pinfunction "+_+") (pintype "passive"))
      (node (ref "IC6") (pin "7") (pinfunction "OUT_7") (pintype "output"))
      (node (ref "R15") (pin "2") (pinfunction "2_2") (pintype "passive"))
    )
    (net (code "50") (name "Net-(J2-LEFT)") (class "Default")
      (node (ref "J2") (pin "TIP") (pinfunction "LEFT_TIP") (pintype "bidirectional"))
      (node (ref "R16") (pin "2") (pinfunction "2_2") (pintype "passive"))
    )
    (net (code "51") (name "Net-(J2-RIGHT)") (class "Default")
      (node (ref "J2") (pin "RING") (pinfunction "RIGHT_RING") (pintype "bidirectional"))
      (node (ref "R17") (pin "2") (pinfunction "2_2") (pintype "passive"))
    )
    (net (code "52") (name "Net-(J4-PadD+)") (class "Default")
      (node (ref "J4") (pin "D+") (pinfunction "D+_D+") (pintype "bidirectional"))
      (node (ref "R22") (pin "1") (pinfunction "1_1") (pintype "passive"))
      (node (ref "R24") (pin "1") (pinfunction "1_1") (pintype "passive"))
    )
    (net (code "53") (name "Net-(J4-PadD-)") (class "Default")
      (node (ref "J4") (pin "D-") (pinfunction "D-_D-") (pintype "bidirectional"))
      (node (ref "R23") (pin "1") (pinfunction "1_1") (pintype "passive"))
    )
    (net (code "54") (name "Net-(J5-Pad2)") (class "Default")
      (node (ref "J5") (pin "2") (pinfunction "2_2") (pintype "bidirectional"))
      (node (ref "U1") (pin "1") (pinfunction "1_1") (pintype "bidirectional"))
    )
    (net (code "55") (name "Net-(J5-Pad3)") (class "Default")
      (node (ref "J5") (pin "3") (pinfunction "3_3") (pintype "bidirectional"))
      (node (ref "U1") (pin "4") (pinfunction "4_4") (pintype "bidirectional"))
    )
    (net (code "56") (name "Net-(J5-Pad4)") (class "Default")
      (node (ref "J5") (pin "4") (pinfunction "4_4") (pintype "bidirectional"))
      (node (ref "U1") (pin "2") (pinfunction "2_2") (pintype "bidirectional"))
    )
    (net (code "57") (name "Net-(J5-Pad5)") (class "Default")
      (node (ref "J5") (pin "5") (pinfunction "5_5") (pintype "bidirectional"))
      (node (ref "U1") (pin "5") (pinfunction "5_5") (pintype "bidirectional"))
    )
    (net (code "58") (name "Net-(J5-Pad6)") (class "Default")
      (node (ref "J5") (pin "6") (pinfunction "6_6") (pintype "bidirectional"))
      (node (ref "U1") (pin "3") (pinfunction "3_3") (pintype "bidirectional"))
    )
    (net (code "59") (name "Net-(J6-Pad2)") (class "Default")
      (node (ref "J6") (pin "2") (pinfunction "2_2") (pintype "bidirectional"))
      (node (ref "U1") (pin "57") (pinfunction "57_57") (pintype "bidirectional"))
    )
    (net (code "60") (name "Net-(J6-Pad3)") (class "Default")
      (node (ref "J6") (pin "3") (pinfunction "3_3") (pintype "bidirectional"))
      (node (ref "U1") (pin "61") (pinfunction "61_61") (pintype "bidirectional"))
    )
    (net (code "61") (name "Net-(J6-Pad4)") (class "Default")
      (node (ref "J6") (pin "4") (pinfunction "4_4") (pintype "bidirectional"))
      (node (ref "U1") (pin "58") (pinfunction "58_58") (pintype "bidirectional"))
    )
    (net (code "62") (name "Net-(J6-Pad5)") (class "Default")
      (node (ref "J6") (pin "5") (pinfunction "5_5") (pintype "bidirectional"))
      (node (ref "U1") (pin "60") (pinfunction "60_60") (pintype "bidirectional"))
    )
    (net (code "63") (name "Net-(J6-Pad6)") (class "Default")
      (node (ref "J6") (pin "6") (pinfunction "6_6") (pintype "bidirectional"))
      (node (ref "U1") (pin "59") (pinfunction "59_59") (pintype "bidirectional"))
    )
    (net (code "64") (name "Net-(J7-Pad1)") (class "Default")
      (node (ref "J7") (pin "1") (pinfunction "1_1") (pintype "passive"))
      (node (ref "U1") (pin "82") (pinfunction "82_82") (pintype "bidirectional"))
    )
    (net (code "65") (name "Net-(J7-Pad2)") (class "Default")
      (node (ref "J7") (pin "2") (pinfunction "2_2") (pintype "passive"))
      (node (ref "U1") (pin "81") (pinfunction "81_81") (pintype "bidirectional"))
    )
    (net (code "66") (name "Net-(J7-Pad3)") (class "Default")
      (node (ref "J7") (pin "3") (pinfunction "3_3") (pintype "passive"))
      (node (ref "U1") (pin "80") (pinfunction "80_80") (pintype "bidirectional"))
    )
    (net (code "67") (name "Net-(J7-Pad4)") (class "Default")
      (node (ref "J7") (pin "4") (pinfunction "4_4") (pintype "passive"))
      (node (ref "U1") (pin "79") (pinfunction "79_79") (pintype "bidirectional"))
    )
    (net (code "68") (name "Net-(J7-Pad5)") (class "Default")
      (node (ref "J7") (pin "5") (pinfunction "5_5") (pintype "passive"))
      (node (ref "U1") (pin "78") (pinfunction "78_78") (pintype "bidirectional"))
    )
    (net (code "69") (name "Net-(J7-Pad6)") (class "Default")
      (node (ref "J7") (pin "6") (pinfunction "6_6") (pintype "passive"))
      (node (ref "U1") (pin "77") (pinfunction "77_77") (pintype "bidirectional"))
    )
    (net (code "70") (name "Net-(J7-Pad7)") (class "Default")
      (node (ref "J7") (pin "7") (pinfunction "7_7") (pintype "passive"))
      (node (ref "U1") (pin "76") (pinfunction "76_76") (pintype "bidirectional"))
    )
    (net (code "71") (name "Net-(J7-Pad8)") (class "Default")
      (node (ref "J7") (pin "8") (pinfunction "8_8") (pintype "passive"))
      (node (ref "U1") (pin "75") (pinfunction "75_75") (pintype "bidirectional"))
    )
    (net (code "72") (name "Net-(J8-Pad1)") (class "Default")
      (node (ref "J8") (pin "1") (pinfunction "1_1") (pintype "passive"))
      (node (ref "U1") (pin "74") (pinfunction "74_74") (pintype "bidirectional"))
    )
    (net (code "73") (name "Net-(J8-Pad2)") (class "Default")
      (node (ref "J8") (pin "2") (pinfunction "2_2") (pintype "passive"))
      (node (ref "U1") (pin "73") (pinfunction "73_73") (pintype "bidirectional"))
    )
    (net (code "74") (name "Net-(J8-Pad3)") (class "Default")
      (node (ref "J8") (pin "3") (pinfunction "3_3") (pintype "passive"))
      (node (ref "U1") (pin "71") (pinfunction "71_71") (pintype "bidirectional"))
    )
    (net (code "75") (name "Net-(J8-Pad4)") (class "Default")
      (node (ref "J8") (pin "4") (pinfunction "4_4") (pintype "passive"))
      (node (ref "U1") (pin "70") (pinfunction "70_70") (pintype "bidirectional"))
    )
    (net (code "76") (name "Net-(J8-Pad5)") (class "Default")
      (node (ref "J8") (pin "5") (pinfunction "5_5") (pintype "passive"))
      (node (ref "U1") (pin "69") (pinfunction "69_69") (pintype "bidirectional"))
    )
    (net (code "77") (name "Net-(J8-Pad6)") (class "Default")
      (node (ref "J8") (pin "6") (pinfunction "6_6") (pintype "passive"))
      (node (ref "U1") (pin "67") (pinfunction "67_67") (pintype "bidirectional"))
    )
    (net (code "78") (name "Net-(J8-Pad7)") (class "Default")
      (node (ref "J8") (pin "7") (pinfunction "7_7") (pintype "passive"))
      (node (ref "U1") (pin "66") (pinfunction "66_66") (pintype "bidirectional"))
    )
    (net (code "79") (name "Net-(J8-Pad8)") (class "Default")
      (node (ref "J8") (pin "8") (pinfunction "8_8") (pintype "passive"))
      (node (ref "U1") (pin "65") (pinfunction "65_65") (pintype "bidirectional"))
    )
    (net (code "80") (name "Net-(J9-Pad2)") (class "Default")
      (node (ref "J9") (pin "2") (pinfunction "2_2") (pintype "bidirectional"))
      (node (ref "U1") (pin "42") (pinfunction "42_42") (pintype "bidirectional"))
    )
    (net (code "81") (name "Net-(J9-Pad3)") (class "Default")
      (node (ref "J9") (pin "3") (pinfunction "3_3") (pintype "bidirectional"))
      (node (ref "U1") (pin "46") (pinfunction "46_46") (pintype "bidirectional"))
    )
    (net (code "82") (name "Net-(J9-Pad4)") (class "Default")
      (node (ref "J9") (pin "4") (pinfunction "4_4") (pintype "bidirectional"))
      (node (ref "U1") (pin "43") (pinfunction "43_43") (pintype "bidirectional"))
    )
    (net (code "83") (name "Net-(J9-Pad5)") (class "Default")
      (node (ref "J9") (pin "5") (pinfunction "5_5") (pintype "bidirectional"))
      (node (ref "U1") (pin "45") (pinfunction "45_45") (pintype "bidirectional"))
    )
    (net (code "84") (name "Net-(J9-Pad6)") (class "Default")
      (node (ref "J9") (pin "6") (pinfunction "6_6") (pintype "bidirectional"))
      (node (ref "U1") (pin "44") (pinfunction "44_44") (pintype "bidirectional"))
    )
    (net (code "85") (name "Net-(JP1-CS)") (class "Default")
      (node (ref "JP1") (pin "2") (pinfunction "CS_2") (pintype "bidirectional"))
      (node (ref "U1") (pin "87") (pinfunction "87_87") (pintype "bidirectional"))
    )
    (net (code "86") (name "Net-(JP1-DI)") (class "Default")
      (node (ref "JP1") (pin "3") (pinfunction "DI_3") (pintype "bidirectional"))
      (node (ref "U1") (pin "88") (pinfunction "88_88") (pintype "bidirectional"))
    )
    (net (code "87") (name "Net-(JP1-DO)") (class "Default")
      (node (ref "JP1") (pin "7") (pinfunction "DO_7") (pintype "bidirectional"))
      (node (ref "U1") (pin "90") (pinfunction "90_90") (pintype "bidirectional"))
    )
    (net (code "88") (name "Net-(JP1-NC)") (class "Default")
      (node (ref "JP1") (pin "1") (pinfunction "NC_1") (pintype "bidirectional"))
      (node (ref "U1") (pin "86") (pinfunction "86_86") (pintype "bidirectional"))
    )
    (net (code "89") (name "Net-(JP1-PadCD2)") (class "Default")
      (node (ref "JP1") (pin "CD2") (pinfunction "CD2_CD2") (pintype "bidirectional"))
      (node (ref "R30") (pin "1") (pinfunction "1_1") (pintype "passive"))
      (node (ref "U1") (pin "84") (pinfunction "84_84") (pintype "bidirectional"))
    )
    (net (code "90") (name "Net-(JP1-RSV)") (class "Default")
      (node (ref "JP1") (pin "8") (pinfunction "RSV_8") (pintype "bidirectional"))
      (node (ref "U1") (pin "91") (pinfunction "91_91") (pintype "bidirectional"))
    )
    (net (code "91") (name "Net-(JP1-SCK)") (class "Default")
      (node (ref "JP1") (pin "5") (pinfunction "SCK_5") (pintype "bidirectional"))
      (node (ref "U1") (pin "89") (pinfunction "89_89") (pintype "bidirectional"))
    )
    (net (code "92") (name "Net-(LED1-PadA)") (class "Default")
      (node (ref "LED1") (pin "A") (pinfunction "A_A") (pintype "passive"))
      (node (ref "R3") (pin "2") (pinfunction "2_2") (pintype "passive"))
    )
    (net (code "93") (name "Net-(LED2-PadA)") (class "Default")
      (node (ref "LED2") (pin "A") (pinfunction "A_A") (pintype "passive"))
      (node (ref "R31") (pin "2") (pinfunction "2_2") (pintype "passive"))
    )
    (net (code "94") (name "Net-(LED3-PadA)") (class "Default")
      (node (ref "LED3") (pin "A") (pinfunction "A_A") (pintype "passive"))
      (node (ref "U1") (pin "101") (pinfunction "101_101") (pintype "bidirectional"))
    )
    (net (code "95") (name "Net-(LED3-PadC)") (class "Default")
      (node (ref "LED3") (pin "C") (pinfunction "C_C") (pintype "passive"))
      (node (ref "R32") (pin "2") (pinfunction "2_2") (pintype "passive"))
    )
    (net (code "96") (name "Net-(R1-Pad2)") (class "Default")
      (node (ref "R1") (pin "2") (pinfunction "2_2") (pintype "passive"))
      (node (ref "R39") (pin "1") (pinfunction "1_1") (pintype "passive"))
      (node (ref "R40") (pin "2") (pinfunction "2_2") (pintype "passive"))
    )
    (net (code "97") (name "Net-(R21-Pad2)") (class "Default")
      (node (ref "R21") (pin "2") (pinfunction "2_2") (pintype "passive"))
      (node (ref "U1") (pin "103") (pinfunction "103_103") (pintype "bidirectional"))
    )
    (net (code "98") (name "Net-(R22-Pad2)") (class "Default")
      (node (ref "R22") (pin "2") (pinfunction "2_2") (pintype "passive"))
      (node (ref "U1") (pin "141") (pinfunction "141_141") (pintype "bidirectional"))
    )
    (net (code "99") (name "Net-(R23-Pad2)") (class "Default")
      (node (ref "R23") (pin "2") (pinfunction "2_2") (pintype "passive"))
      (node (ref "U1") (pin "140") (pinfunction "140_140") (pintype "bidirectional"))
    )
    (net (code "100") (name "Net-(R24-Pad2)") (class "Default")
      (node (ref "R24") (pin "2") (pinfunction "2_2") (pintype "passive"))
      (node (ref "U1") (pin "142") (pinfunction "142_142") (pintype "bidirectional"))
    )
    (net (code "101") (name "Net-(R31-Pad1)") (class "Default")
      (node (ref "R31") (pin "1") (pinfunction "1_1") (pintype "passive"))
      (node (ref "U1") (pin "144") (pinfunction "144_144") (pintype "bidirectional"))
    )
    (net (code "102") (name "Net-(U2-AOUTL)") (class "Default")
      (node (ref "R11") (pin "1") (pinfunction "1_1") (pintype "passive"))
      (node (ref "U2") (pin "7") (pinfunction "AOUTL_7") (pintype "bidirectional"))
    )
    (net (code "103") (name "Net-(U2-AOUTR)") (class "Default")
      (node (ref "R10") (pin "1") (pinfunction "1_1") (pintype "passive"))
      (node (ref "U2") (pin "10") (pinfunction "AOUTR_10") (pintype "bidirectional"))
    )
    (net (code "104") (name "Net-(U2-FILT+)") (class "Default")
      (node (ref "C33") (pin "1") (pinfunction "1_1") (pintype "passive"))
      (node (ref "U2") (pin "6") (pinfunction "FILT+_6") (pintype "bidirectional"))
    )
    (net (code "105") (name "PROGRAM") (class "Default")
      (node (ref "R25") (pin "2") (pinfunction "2_2") (pintype "passive"))
      (node (ref "R29") (pin "1") (pinfunction "1_1") (pintype "passive"))
      (node (ref "U1") (pin "10") (pinfunction "10_10") (pintype "bidirectional"))
      (node (ref "U1") (pin "13") (pinfunction "/PROGRAM_13") (pintype "bidirectional"))
    )
    (net (code "106") (name "RESET_N") (class "Default")
      (node (ref "C41") (pin "1") (pinfunction "1_1") (pintype "passive"))
      (node (ref "R28") (pin "1") (pinfunction "1_1") (pintype "passive"))
      (node (ref "S1") (pin "3") (pinfunction "S_3") (pintype "passive"))
      (node (ref "S1") (pin "4") (pinfunction "S1_4") (pintype "passive"))
      (node (ref "U1") (pin "36") (pinfunction "36_36") (pintype "bidirectional"))
    )
    (net (code "107") (name "SYSCLK") (class "Default")
      (node (ref "IC2") (pin "8") (pinfunction "O_8") (pintype "output"))
      (node (ref "U1") (pin "92") (pinfunction "92_92") (pintype "bidirectional"))
    )
    (net (code "108") (name "V+") (class "Default")
      (node (ref "C35") (pin "1") (pinfunction "1_1") (pintype "passive"))
      (node (ref "C36") (pin "1") (pinfunction "1_1") (pintype "passive"))
      (node (ref "IC6") (pin "8") (pinfunction "V+_8") (pintype "power_in"))
      (node (ref "L1") (pin "2") (pinfunction "2_2") (pintype "passive"))
      (node (ref "U2") (pin "9") (pinfunction "VA_9") (pintype "bidirectional"))
    )
    (net (code "109") (name "VCCINT") (class "Default")
      (node (ref "C1") (pin "2") (pinfunction "2_2") (pintype "passive"))
      (node (ref "C14") (pin "1") (pinfunction "1_1") (pintype "passive"))
      (node (ref "C15") (pin "1") (pinfunction "1_1") (pintype "passive"))
      (node (ref "C16") (pin "1") (pinfunction "1_1") (pintype "passive"))
      (node (ref "C17") (pin "1") (pinfunction "1_1") (pintype "passive"))
      (node (ref "C18") (pin "1") (pinfunction "1_1") (pintype "passive"))
      (node (ref "C19") (pin "1") (pinfunction "1_1") (pintype "passive"))
      (node (ref "C27") (pin "2") (pinfunction "2_2") (pintype "passive"))
      (node (ref "L2") (pin "1") (pinfunction "1_1") (pintype "passive"))
      (node (ref "R4") (pin "1") (pinfunction "1_1") (pintype "passive"))
      (node (ref "R40") (pin "1") (pinfunction "1_1") (pintype "passive"))
      (node (ref "R5") (pin "1") (pinfunction "1_1") (pintype "passive"))
      (node (ref "TP2") (pin "1") (pinfunction "1_1") (pintype "passive"))
      (node (ref "U1") (pin "117") (pinfunction "VCORE_5_117") (pintype "bidirectional"))
      (node (ref "U1") (pin "132") (pinfunction "VCORE_3_132") (pintype "bidirectional"))
      (node (ref "U1") (pin "143") (pinfunction "VCORE_4_143") (pintype "bidirectional"))
      (node (ref "U1") (pin "38") (pinfunction "VCORE_38") (pintype "bidirectional"))
      (node (ref "U1") (pin "47") (pinfunction "VCORE1_47") (pintype "bidirectional"))
      (node (ref "U1") (pin "63") (pinfunction "VCORE2_63") (pintype "bidirectional"))
    )
    (net (code "110") (name "VCC_PLL0") (class "Default")
      (node (ref "C21") (pin "1") (pinfunction "1_1") (pintype "passive"))
      (node (ref "R5") (pin "2") (pinfunction "2_2") (pintype "passive"))
      (node (ref "U1") (pin "109") (pinfunction "VCC_PLL_109") (pintype "bidirectional"))
    )
    (net (code "111") (name "VCC_PLL1") (class "Default")
      (node (ref "C20") (pin "1") (pinfunction "1_1") (pintype "passive"))
      (node (ref "R4") (pin "2") (pinfunction "2_2") (pintype "passive"))
      (node (ref "U1") (pin "37") (pinfunction "VCC_PLL1_37") (pintype "bidirectional"))
    )
    (net (code "112") (name "VQ") (class "Default")
      (node (ref "C32") (pin "1") (pinfunction "1_1") (pintype "passive"))
      (node (ref "C34") (pin "1") (pinfunction "1_1") (pintype "passive"))
      (node (ref "IC6") (pin "3") (pinfunction "+IN_3") (pintype "input"))
      (node (ref "IC6") (pin "5") (pinfunction "+IN_5") (pintype "input"))
      (node (ref "U2") (pin "5") (pinfunction "VQ_5") (pintype "bidirectional"))
    )
    (net (code "113") (name "unconnected-(IC2C-O-Pad6)") (class "Default")
      (node (ref "IC2") (pin "6") (pinfunction "O_6") (pintype "output"))
    )
    (net (code "114") (name "unconnected-(IC2F-O-Pad12)") (class "Default")
      (node (ref "IC2") (pin "12") (pinfunction "O_12") (pintype "output"))
    )
    (net (code "115") (name "unconnected-(J5-Pad1)") (class "Default")
      (node (ref "J5") (pin "1") (pinfunction "1_1") (pintype "bidirectional"))
    )
    (net (code "116") (name "unconnected-(JP1-PadCD1)") (class "Default")
      (node (ref "JP1") (pin "CD1") (pinfunction "CD1_CD1") (pintype "bidirectional"))
    )
    (net (code "117") (name "unconnected-(U1-GCLKION_1-Pad23)") (class "Default")
      (node (ref "U1") (pin "23") (pinfunction "GCLKION_1_23") (pintype "bidirectional"))
    )
    (net (code "118") (name "unconnected-(U1-Pad7)") (class "Default")
      (node (ref "U1") (pin "7") (pinfunction "7_7") (pintype "bidirectional"))
    )
    (net (code "119") (name "unconnected-(U1-Pad18)") (class "Default")
      (node (ref "U1") (pin "18") (pinfunction "18_18") (pintype "bidirectional"))
    )
    (net (code "120") (name "unconnected-(U1-Pad19)") (class "Default")
      (node (ref "U1") (pin "19") (pinfunction "19_19") (pintype "bidirectional"))
    )
    (net (code "121") (name "unconnected-(U1-Pad24)") (class "Default")
      (node (ref "U1") (pin "24") (pinfunction "24_24") (pintype "bidirectional"))
    )
    (net (code "122") (name "unconnected-(U1-Pad25)") (class "Default")
      (node (ref "U1") (pin "25") (pinfunction "25_25") (pintype "bidirectional"))
    )
    (net (code "123") (name "unconnected-(U1-Pad26)") (class "Default")
      (node (ref "U1") (pin "26") (pinfunction "26_26") (pintype "bidirectional"))
    )
    (net (code "124") (name "unconnected-(U1-Pad28)") (class "Default")
      (node (ref "U1") (pin "28") (pinfunction "28_28") (pintype "bidirectional"))
    )
    (net (code "125") (name "unconnected-(U1-Pad29)") (class "Default")
      (node (ref "U1") (pin "29") (pinfunction "29_29") (pintype "bidirectional"))
    )
    (net (code "126") (name "unconnected-(U1-Pad39)") (class "Default")
      (node (ref "U1") (pin "39") (pinfunction "39_39") (pintype "bidirectional"))
    )
    (net (code "127") (name "unconnected-(U1-Pad40)") (class "Default")
      (node (ref "U1") (pin "40") (pinfunction "40_40") (pintype "bidirectional"))
    )
    (net (code "128") (name "unconnected-(U1-Pad48)") (class "Default")
      (node (ref "U1") (pin "48") (pinfunction "48_48") (pintype "bidirectional"))
    )
    (net (code "129") (name "unconnected-(U1-Pad51)") (class "Default")
      (node (ref "U1") (pin "51") (pinfunction "51_51") (pintype "bidirectional"))
    )
    (net (code "130") (name "unconnected-(U1-Pad52)") (class "Default")
      (node (ref "U1") (pin "52") (pinfunction "52_52") (pintype "bidirectional"))
    )
    (net (code "131") (name "unconnected-(U1-Pad53)") (class "Default")
      (node (ref "U1") (pin "53") (pinfunction "53_53") (pintype "bidirectional"))
    )
    (net (code "132") (name "unconnected-(U1-Pad54)") (class "Default")
      (node (ref "U1") (pin "54") (pinfunction "54_54") (pintype "bidirectional"))
    )
    (net (code "133") (name "unconnected-(U1-Pad55)") (class "Default")
      (node (ref "U1") (pin "55") (pinfunction "55_55") (pintype "bidirectional"))
    )
    (net (code "134") (name "unconnected-(U1-Pad62)") (class "Default")
      (node (ref "U1") (pin "62") (pinfunction "62_62") (pintype "bidirectional"))
    )
    (net (code "135") (name "unconnected-(U1-Pad85)") (class "Default")
      (node (ref "U1") (pin "85") (pinfunction "85_85") (pintype "bidirectional"))
    )
    (net (code "136") (name "unconnected-(U1-Pad93)") (class "Default")
      (node (ref "U1") (pin "93") (pinfunction "93_93") (pintype "bidirectional"))
    )
    (net (code "137") (name "unconnected-(U1-Pad96)") (class "Default")
      (node (ref "U1") (pin "96") (pinfunction "96_96") (pintype "bidirectional"))
    )
    (net (code "138") (name "unconnected-(U1-Pad97)") (class "Default")
      (node (ref "U1") (pin "97") (pinfunction "97_97") (pintype "bidirectional"))
    )
    (net (code "139") (name "unconnected-(U1-Pad98)") (class "Default")
      (node (ref "U1") (pin "98") (pinfunction "98_98") (pintype "bidirectional"))
    )
    (net (code "140") (name "unconnected-(U1-Pad99)") (class "Default")
      (node (ref "U1") (pin "99") (pinfunction "99_99") (pintype "bidirectional"))
    )
    (net (code "141") (name "unconnected-(U1-Pad100)") (class "Default")
      (node (ref "U1") (pin "100") (pinfunction "100_100") (pintype "bidirectional"))
    )
    (net (code "142") (name "unconnected-(U1-Pad102)") (class "Default")
      (node (ref "U1") (pin "102") (pinfunction "102_102") (pintype "bidirectional"))
    )
    (net (code "143") (name "unconnected-(U1-Pad107)") (class "Default")
      (node (ref "U1") (pin "107") (pinfunction "107_107") (pintype "bidirectional"))
    )
    (net (code "144") (name "unconnected-(U1-Pad108)") (class "Default")
      (node (ref "U1") (pin "108") (pinfunction "108_108") (pintype "bidirectional"))
    )
    (net (code "145") (name "unconnected-(U1-Pad110)") (class "Default")
      (node (ref "U1") (pin "110") (pinfunction "110_110") (pintype "bidirectional"))
    )
    (net (code "146") (name "unconnected-(U1-Pad111)") (class "Default")
      (node (ref "U1") (pin "111") (pinfunction "111_111") (pintype "bidirectional"))
    )
    (net (code "147") (name "unconnected-(U1-Pad112)") (class "Default")
      (node (ref "U1") (pin "112") (pinfunction "112_112") (pintype "bidirectional"))
    )
    (net (code "148") (name "unconnected-(U1-Pad113)") (class "Default")
      (node (ref "U1") (pin "113") (pinfunction "113_113") (pintype "bidirectional"))
    )
    (net (code "149") (name "unconnected-(U1-Pad115)") (class "Default")
      (node (ref "U1") (pin "115") (pinfunction "115_115") (pintype "bidirectional"))
    )
    (net (code "150") (name "unconnected-(U1-Pad116)") (class "Default")
      (node (ref "U1") (pin "116") (pinfunction "116_116") (pintype "bidirectional"))
    )
    (net (code "151") (name "unconnected-(U1-Pad118)") (class "Default")
      (node (ref "U1") (pin "118") (pinfunction "118_118") (pintype "bidirectional"))
    )
    (net (code "152") (name "unconnected-(U1-Pad119)") (class "Default")
      (node (ref "U1") (pin "119") (pinfunction "119_119") (pintype "bidirectional"))
    )
    (net (code "153") (name "unconnected-(U1-Pad121)") (class "Default")
      (node (ref "U1") (pin "121") (pinfunction "121_121") (pintype "bidirectional"))
    )
    (net (code "154") (name "unconnected-(U1-Pad122)") (class "Default")
      (node (ref "U1") (pin "122") (pinfunction "122_122") (pintype "bidirectional"))
    )
    (net (code "155") (name "unconnected-(U1-Pad123)") (class "Default")
      (node (ref "U1") (pin "123") (pinfunction "123_123") (pintype "bidirectional"))
    )
    (net (code "156") (name "unconnected-(U1-Pad124)") (class "Default")
      (node (ref "U1") (pin "124") (pinfunction "124_124") (pintype "bidirectional"))
    )
    (net (code "157") (name "unconnected-(U1-Pad125)") (class "Default")
      (node (ref "U1") (pin "125") (pinfunction "125_125") (pintype "bidirectional"))
    )
    (net (code "158") (name "unconnected-(U1-Pad126)") (class "Default")
      (node (ref "U1") (pin "126") (pinfunction "126_126") (pintype "bidirectional"))
    )
    (net (code "159") (name "unconnected-(U1-Pad127)") (class "Default")
      (node (ref "U1") (pin "127") (pinfunction "127_127") (pintype "bidirectional"))
    )
    (net (code "160") (name "unconnected-(U1-Pad131)") (class "Default")
      (node (ref "U1") (pin "131") (pinfunction "131_131") (pintype "bidirectional"))
    )
    (net (code "161") (name "unconnected-(U1-Pad133)") (class "Default")
      (node (ref "U1") (pin "133") (pinfunction "133_133") (pintype "bidirectional"))
    )
    (net (code "162") (name "unconnected-(U1-Pad134)") (class "Default")
      (node (ref "U1") (pin "134") (pinfunction "134_134") (pintype "bidirectional"))
    )
    (net (code "163") (name "unconnected-(U1-Pad135)") (class "Default")
      (node (ref "U1") (pin "135") (pinfunction "135_135") (pintype "bidirectional"))
    )
    (net (code "164") (name "{slash}INIT") (class "Default")
      (node (ref "R26") (pin "2") (pinfunction "2_2") (pintype "passive"))
      (node (ref "U1") (pin "9") (pinfunction "/INIT_9") (pintype "bidirectional"))
    )
  )
)
